# Schaltplan.net
KiCad netlist of a schematic drawn in EAGLE
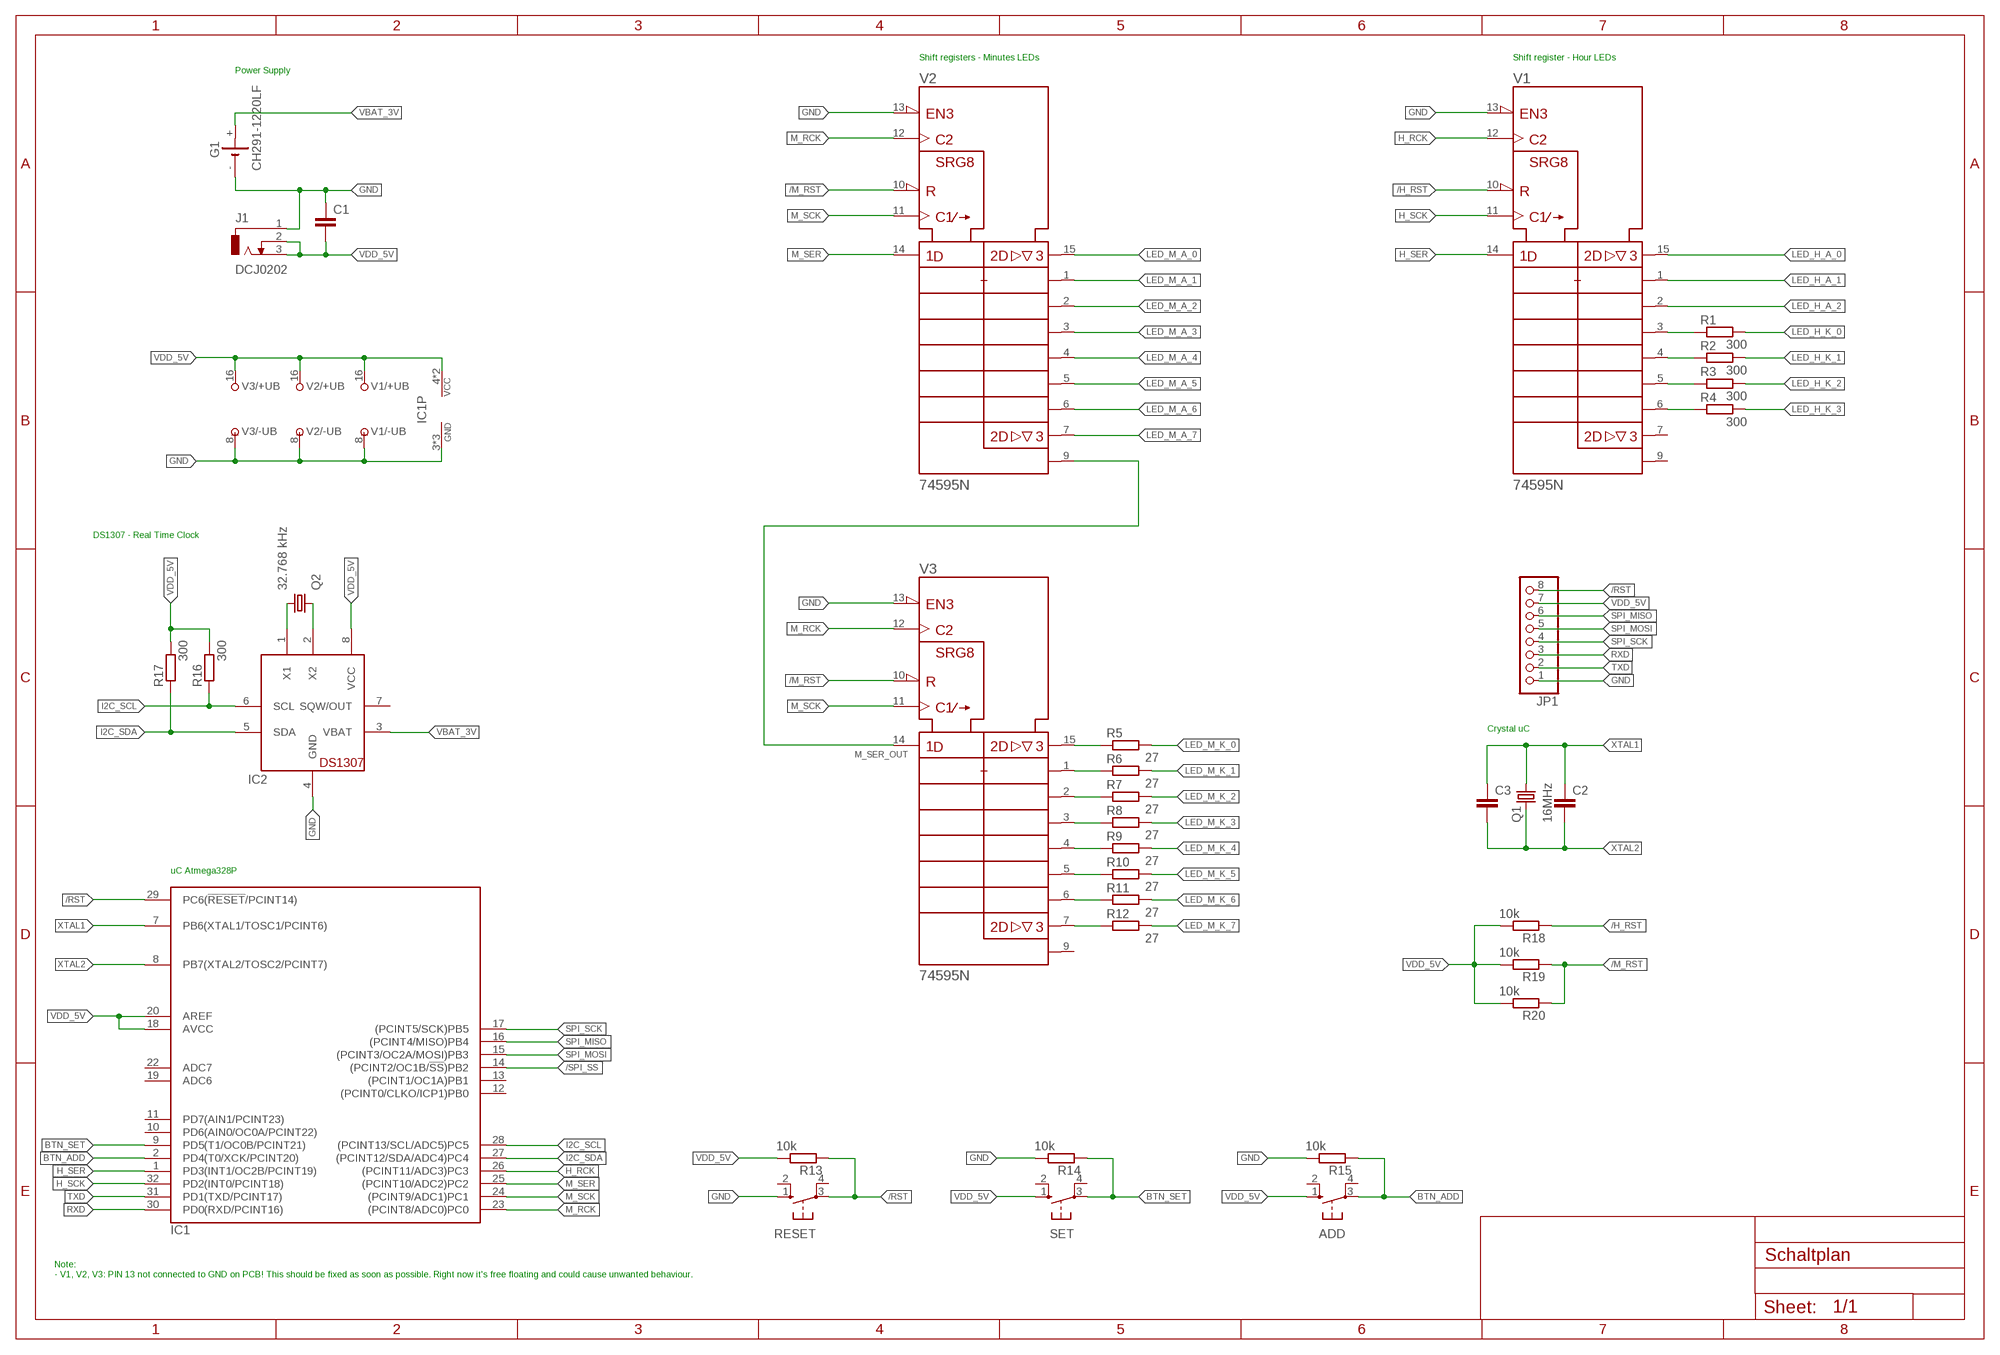
[diagram p0: schematic, sheet 1, part 1 of 2]
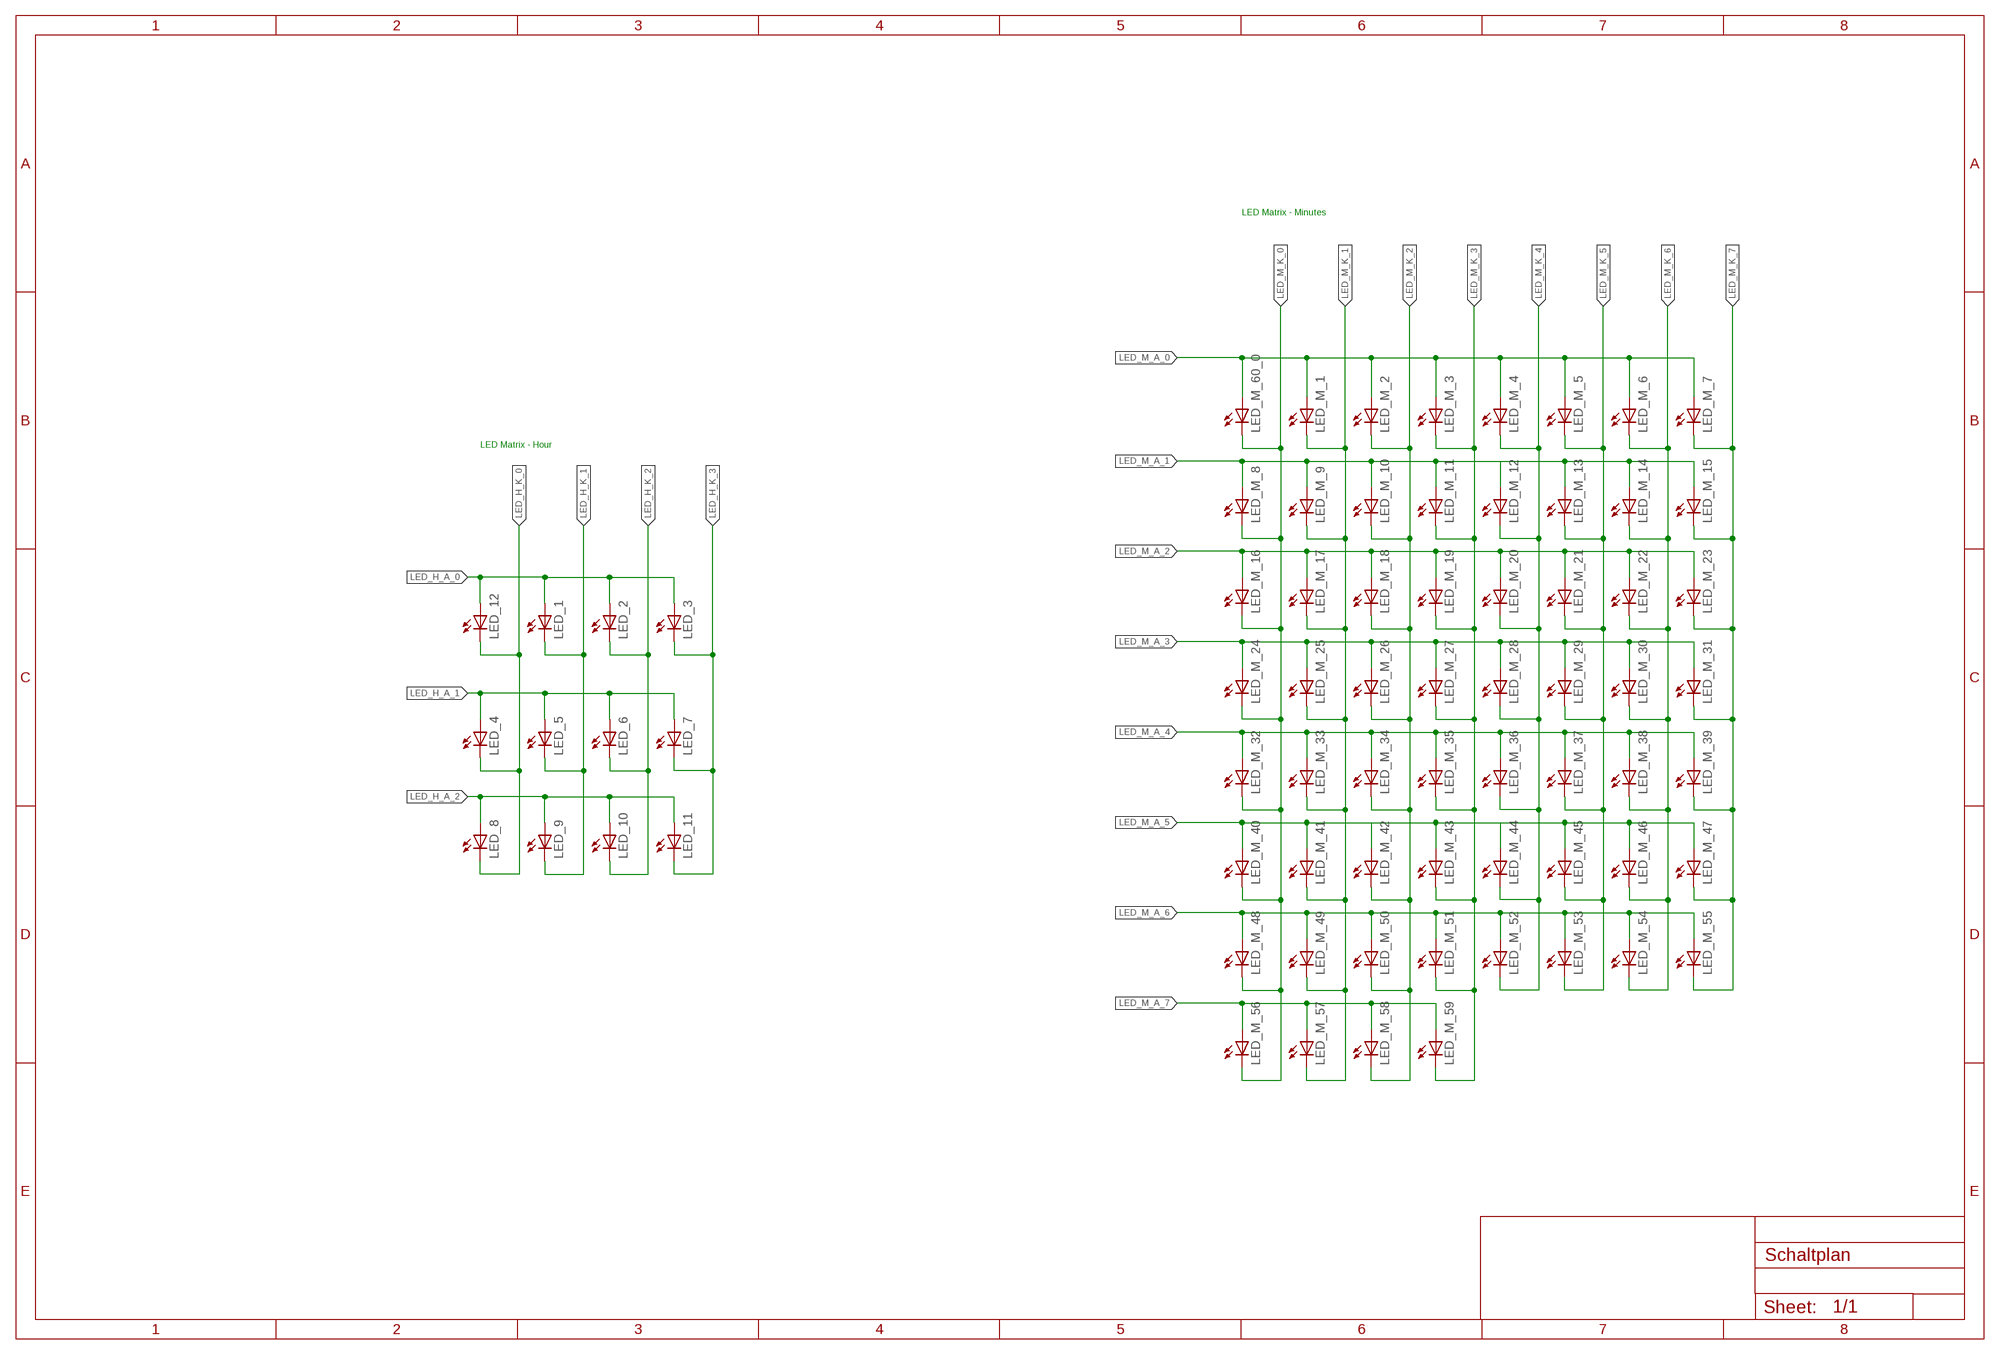
[diagram p1: schematic, sheet 1, part 2 of 2]

(export (version "E")
  (design (tool "Eeschema 10.0.6"))
  (components
    (comp (ref "ADD")
      (value "10-XX")
      (footprint "eagle-import:B3F-10XX")
      (fields (field (name "MPN") "B3F-1000"))
      (libsource (lib "eagle-import") (part "10-XX"))
    )
    (comp (ref "C1")
      (value "C-EUC1206")
      (footprint "eagle-import:C1206")
      (libsource (lib "eagle-import") (part "C-EUC1206"))
    )
    (comp (ref "C2")
      (value "C-EUC1206")
      (footprint "eagle-import:C1206")
      (libsource (lib "eagle-import") (part "C-EUC1206"))
    )
    (comp (ref "C3")
      (value "C-EUC1206")
      (footprint "eagle-import:C1206")
      (libsource (lib "eagle-import") (part "C-EUC1206"))
    )
    (comp (ref "G1")
      (value "CH291-1220LF")
      (footprint "eagle-import:CH291-1220LF")
      (libsource (lib "eagle-import") (part "CH291-1220LF"))
    )
    (comp (ref "IC1")
      (value "ATMEGA328P-AN")
      (footprint "eagle-import:QFP32_7X7_0.80")
      (libsource (lib "eagle-import") (part "ATMEGA8P-AN32"))
    )
    (comp (ref "IC2")
      (value "DS1307")
      (footprint "eagle-import:DIL08")
      (libsource (lib "eagle-import") (part "DS1307"))
    )
    (comp (ref "J1")
      (value "DCJ0202")
      (footprint "eagle-import:DCJ0202")
      (libsource (lib "eagle-import") (part "DCJ0202"))
    )
    (comp (ref "JP1")
      (value "PINHD-1X8")
      (footprint "eagle-import:1X08")
      (libsource (lib "eagle-import") (part "PINHD-1X8"))
    )
    (comp (ref "LED_1")
      (value "LED5MM")
      (footprint "eagle-import:LED5MM")
      (libsource (lib "eagle-import") (part "LED5MM"))
    )
    (comp (ref "LED_2")
      (value "LED5MM")
      (footprint "eagle-import:LED5MM")
      (libsource (lib "eagle-import") (part "LED5MM"))
    )
    (comp (ref "LED_3")
      (value "LED5MM")
      (footprint "eagle-import:LED5MM")
      (libsource (lib "eagle-import") (part "LED5MM"))
    )
    (comp (ref "LED_4")
      (value "LED5MM")
      (footprint "eagle-import:LED5MM")
      (libsource (lib "eagle-import") (part "LED5MM"))
    )
    (comp (ref "LED_5")
      (value "LED5MM")
      (footprint "eagle-import:LED5MM")
      (libsource (lib "eagle-import") (part "LED5MM"))
    )
    (comp (ref "LED_6")
      (value "LED5MM")
      (footprint "eagle-import:LED5MM")
      (libsource (lib "eagle-import") (part "LED5MM"))
    )
    (comp (ref "LED_7")
      (value "LED5MM")
      (footprint "eagle-import:LED5MM")
      (libsource (lib "eagle-import") (part "LED5MM"))
    )
    (comp (ref "LED_8")
      (value "LED5MM")
      (footprint "eagle-import:LED5MM")
      (libsource (lib "eagle-import") (part "LED5MM"))
    )
    (comp (ref "LED_9")
      (value "LED5MM")
      (footprint "eagle-import:LED5MM")
      (libsource (lib "eagle-import") (part "LED5MM"))
    )
    (comp (ref "LED_10")
      (value "LED5MM")
      (footprint "eagle-import:LED5MM")
      (libsource (lib "eagle-import") (part "LED5MM"))
    )
    (comp (ref "LED_11")
      (value "LED5MM")
      (footprint "eagle-import:LED5MM")
      (libsource (lib "eagle-import") (part "LED5MM"))
    )
    (comp (ref "LED_12")
      (value "LED5MM")
      (footprint "eagle-import:LED5MM")
      (libsource (lib "eagle-import") (part "LED5MM"))
    )
    (comp (ref "LED_M_1")
      (value "LED5MM")
      (footprint "eagle-import:LED5MM")
      (libsource (lib "eagle-import") (part "LED5MM"))
    )
    (comp (ref "LED_M_2")
      (value "LED5MM")
      (footprint "eagle-import:LED5MM")
      (libsource (lib "eagle-import") (part "LED5MM"))
    )
    (comp (ref "LED_M_3")
      (value "LED5MM")
      (footprint "eagle-import:LED5MM")
      (libsource (lib "eagle-import") (part "LED5MM"))
    )
    (comp (ref "LED_M_4")
      (value "LED5MM")
      (footprint "eagle-import:LED5MM")
      (libsource (lib "eagle-import") (part "LED5MM"))
    )
    (comp (ref "LED_M_5")
      (value "LED5MM")
      (footprint "eagle-import:LED5MM")
      (libsource (lib "eagle-import") (part "LED5MM"))
    )
    (comp (ref "LED_M_6")
      (value "LED5MM")
      (footprint "eagle-import:LED5MM")
      (libsource (lib "eagle-import") (part "LED5MM"))
    )
    (comp (ref "LED_M_7")
      (value "LED5MM")
      (footprint "eagle-import:LED5MM")
      (libsource (lib "eagle-import") (part "LED5MM"))
    )
    (comp (ref "LED_M_8")
      (value "LED5MM")
      (footprint "eagle-import:LED5MM")
      (libsource (lib "eagle-import") (part "LED5MM"))
    )
    (comp (ref "LED_M_9")
      (value "LED5MM")
      (footprint "eagle-import:LED5MM")
      (libsource (lib "eagle-import") (part "LED5MM"))
    )
    (comp (ref "LED_M_10")
      (value "LED5MM")
      (footprint "eagle-import:LED5MM")
      (libsource (lib "eagle-import") (part "LED5MM"))
    )
    (comp (ref "LED_M_11")
      (value "LED5MM")
      (footprint "eagle-import:LED5MM")
      (libsource (lib "eagle-import") (part "LED5MM"))
    )
    (comp (ref "LED_M_12")
      (value "LED5MM")
      (footprint "eagle-import:LED5MM")
      (libsource (lib "eagle-import") (part "LED5MM"))
    )
    (comp (ref "LED_M_13")
      (value "LED5MM")
      (footprint "eagle-import:LED5MM")
      (libsource (lib "eagle-import") (part "LED5MM"))
    )
    (comp (ref "LED_M_14")
      (value "LED5MM")
      (footprint "eagle-import:LED5MM")
      (libsource (lib "eagle-import") (part "LED5MM"))
    )
    (comp (ref "LED_M_15")
      (value "LED5MM")
      (footprint "eagle-import:LED5MM")
      (libsource (lib "eagle-import") (part "LED5MM"))
    )
    (comp (ref "LED_M_16")
      (value "LED5MM")
      (footprint "eagle-import:LED5MM")
      (libsource (lib "eagle-import") (part "LED5MM"))
    )
    (comp (ref "LED_M_17")
      (value "LED5MM")
      (footprint "eagle-import:LED5MM")
      (libsource (lib "eagle-import") (part "LED5MM"))
    )
    (comp (ref "LED_M_18")
      (value "LED5MM")
      (footprint "eagle-import:LED5MM")
      (libsource (lib "eagle-import") (part "LED5MM"))
    )
    (comp (ref "LED_M_19")
      (value "LED5MM")
      (footprint "eagle-import:LED5MM")
      (libsource (lib "eagle-import") (part "LED5MM"))
    )
    (comp (ref "LED_M_20")
      (value "LED5MM")
      (footprint "eagle-import:LED5MM")
      (libsource (lib "eagle-import") (part "LED5MM"))
    )
    (comp (ref "LED_M_21")
      (value "LED5MM")
      (footprint "eagle-import:LED5MM")
      (libsource (lib "eagle-import") (part "LED5MM"))
    )
    (comp (ref "LED_M_22")
      (value "LED5MM")
      (footprint "eagle-import:LED5MM")
      (libsource (lib "eagle-import") (part "LED5MM"))
    )
    (comp (ref "LED_M_23")
      (value "LED5MM")
      (footprint "eagle-import:LED5MM")
      (libsource (lib "eagle-import") (part "LED5MM"))
    )
    (comp (ref "LED_M_24")
      (value "LED5MM")
      (footprint "eagle-import:LED5MM")
      (libsource (lib "eagle-import") (part "LED5MM"))
    )
    (comp (ref "LED_M_25")
      (value "LED5MM")
      (footprint "eagle-import:LED5MM")
      (libsource (lib "eagle-import") (part "LED5MM"))
    )
    (comp (ref "LED_M_26")
      (value "LED5MM")
      (footprint "eagle-import:LED5MM")
      (libsource (lib "eagle-import") (part "LED5MM"))
    )
    (comp (ref "LED_M_27")
      (value "LED5MM")
      (footprint "eagle-import:LED5MM")
      (libsource (lib "eagle-import") (part "LED5MM"))
    )
    (comp (ref "LED_M_28")
      (value "LED5MM")
      (footprint "eagle-import:LED5MM")
      (libsource (lib "eagle-import") (part "LED5MM"))
    )
    (comp (ref "LED_M_29")
      (value "LED5MM")
      (footprint "eagle-import:LED5MM")
      (libsource (lib "eagle-import") (part "LED5MM"))
    )
    (comp (ref "LED_M_30")
      (value "LED5MM")
      (footprint "eagle-import:LED5MM")
      (libsource (lib "eagle-import") (part "LED5MM"))
    )
    (comp (ref "LED_M_31")
      (value "LED5MM")
      (footprint "eagle-import:LED5MM")
      (libsource (lib "eagle-import") (part "LED5MM"))
    )
    (comp (ref "LED_M_32")
      (value "LED5MM")
      (footprint "eagle-import:LED5MM")
      (libsource (lib "eagle-import") (part "LED5MM"))
    )
    (comp (ref "LED_M_33")
      (value "LED5MM")
      (footprint "eagle-import:LED5MM")
      (libsource (lib "eagle-import") (part "LED5MM"))
    )
    (comp (ref "LED_M_34")
      (value "LED5MM")
      (footprint "eagle-import:LED5MM")
      (libsource (lib "eagle-import") (part "LED5MM"))
    )
    (comp (ref "LED_M_35")
      (value "LED5MM")
      (footprint "eagle-import:LED5MM")
      (libsource (lib "eagle-import") (part "LED5MM"))
    )
    (comp (ref "LED_M_36")
      (value "LED5MM")
      (footprint "eagle-import:LED5MM")
      (libsource (lib "eagle-import") (part "LED5MM"))
    )
    (comp (ref "LED_M_37")
      (value "LED5MM")
      (footprint "eagle-import:LED5MM")
      (libsource (lib "eagle-import") (part "LED5MM"))
    )
    (comp (ref "LED_M_38")
      (value "LED5MM")
      (footprint "eagle-import:LED5MM")
      (libsource (lib "eagle-import") (part "LED5MM"))
    )
    (comp (ref "LED_M_39")
      (value "LED5MM")
      (footprint "eagle-import:LED5MM")
      (libsource (lib "eagle-import") (part "LED5MM"))
    )
    (comp (ref "LED_M_40")
      (value "LED5MM")
      (footprint "eagle-import:LED5MM")
      (libsource (lib "eagle-import") (part "LED5MM"))
    )
    (comp (ref "LED_M_41")
      (value "LED5MM")
      (footprint "eagle-import:LED5MM")
      (libsource (lib "eagle-import") (part "LED5MM"))
    )
    (comp (ref "LED_M_42")
      (value "LED5MM")
      (footprint "eagle-import:LED5MM")
      (libsource (lib "eagle-import") (part "LED5MM"))
    )
    (comp (ref "LED_M_43")
      (value "LED5MM")
      (footprint "eagle-import:LED5MM")
      (libsource (lib "eagle-import") (part "LED5MM"))
    )
    (comp (ref "LED_M_44")
      (value "LED5MM")
      (footprint "eagle-import:LED5MM")
      (libsource (lib "eagle-import") (part "LED5MM"))
    )
    (comp (ref "LED_M_45")
      (value "LED5MM")
      (footprint "eagle-import:LED5MM")
      (libsource (lib "eagle-import") (part "LED5MM"))
    )
    (comp (ref "LED_M_46")
      (value "LED5MM")
      (footprint "eagle-import:LED5MM")
      (libsource (lib "eagle-import") (part "LED5MM"))
    )
    (comp (ref "LED_M_47")
      (value "LED5MM")
      (footprint "eagle-import:LED5MM")
      (libsource (lib "eagle-import") (part "LED5MM"))
    )
    (comp (ref "LED_M_48")
      (value "LED5MM")
      (footprint "eagle-import:LED5MM")
      (libsource (lib "eagle-import") (part "LED5MM"))
    )
    (comp (ref "LED_M_49")
      (value "LED5MM")
      (footprint "eagle-import:LED5MM")
      (libsource (lib "eagle-import") (part "LED5MM"))
    )
    (comp (ref "LED_M_50")
      (value "LED5MM")
      (footprint "eagle-import:LED5MM")
      (libsource (lib "eagle-import") (part "LED5MM"))
    )
    (comp (ref "LED_M_51")
      (value "LED5MM")
      (footprint "eagle-import:LED5MM")
      (libsource (lib "eagle-import") (part "LED5MM"))
    )
    (comp (ref "LED_M_52")
      (value "LED5MM")
      (footprint "eagle-import:LED5MM")
      (libsource (lib "eagle-import") (part "LED5MM"))
    )
    (comp (ref "LED_M_53")
      (value "LED5MM")
      (footprint "eagle-import:LED5MM")
      (libsource (lib "eagle-import") (part "LED5MM"))
    )
    (comp (ref "LED_M_54")
      (value "LED5MM")
      (footprint "eagle-import:LED5MM")
      (libsource (lib "eagle-import") (part "LED5MM"))
    )
    (comp (ref "LED_M_55")
      (value "LED5MM")
      (footprint "eagle-import:LED5MM")
      (libsource (lib "eagle-import") (part "LED5MM"))
    )
    (comp (ref "LED_M_56")
      (value "LED5MM")
      (footprint "eagle-import:LED5MM")
      (libsource (lib "eagle-import") (part "LED5MM"))
    )
    (comp (ref "LED_M_57")
      (value "LED5MM")
      (footprint "eagle-import:LED5MM")
      (libsource (lib "eagle-import") (part "LED5MM"))
    )
    (comp (ref "LED_M_58")
      (value "LED5MM")
      (footprint "eagle-import:LED5MM")
      (libsource (lib "eagle-import") (part "LED5MM"))
    )
    (comp (ref "LED_M_59")
      (value "LED5MM")
      (footprint "eagle-import:LED5MM")
      (libsource (lib "eagle-import") (part "LED5MM"))
    )
    (comp (ref "LED_M_60_0")
      (value "LED5MM")
      (footprint "eagle-import:LED5MM")
      (libsource (lib "eagle-import") (part "LED5MM"))
    )
    (comp (ref "Q1")
      (value "16MHz")
      (footprint "eagle-import:HC49UP")
      (libsource (lib "eagle-import") (part "CRYSTALHC49UP"))
    )
    (comp (ref "Q2")
      (value "32.768 kHz")
      (footprint "eagle-import:TC26V")
      (libsource (lib "eagle-import") (part "crystal_204_CRYSTALTC26V"))
    )
    (comp (ref "R1")
      (value "300")
      (footprint "eagle-import:R5025")
      (libsource (lib "eagle-import") (part "R-EU_R5025"))
    )
    (comp (ref "R2")
      (value "300")
      (footprint "eagle-import:R5025")
      (libsource (lib "eagle-import") (part "R-EU_R5025"))
    )
    (comp (ref "R3")
      (value "300")
      (footprint "eagle-import:R5025")
      (libsource (lib "eagle-import") (part "R-EU_R5025"))
    )
    (comp (ref "R4")
      (value "300")
      (footprint "eagle-import:R5025")
      (libsource (lib "eagle-import") (part "R-EU_R5025"))
    )
    (comp (ref "R5")
      (value "27")
      (footprint "eagle-import:R5025")
      (libsource (lib "eagle-import") (part "R-EU_R5025"))
    )
    (comp (ref "R6")
      (value "27")
      (footprint "eagle-import:R5025")
      (libsource (lib "eagle-import") (part "R-EU_R5025"))
    )
    (comp (ref "R7")
      (value "27")
      (footprint "eagle-import:R5025")
      (libsource (lib "eagle-import") (part "R-EU_R5025"))
    )
    (comp (ref "R8")
      (value "27")
      (footprint "eagle-import:R5025")
      (libsource (lib "eagle-import") (part "R-EU_R5025"))
    )
    (comp (ref "R9")
      (value "27")
      (footprint "eagle-import:R5025")
      (libsource (lib "eagle-import") (part "R-EU_R5025"))
    )
    (comp (ref "R10")
      (value "27")
      (footprint "eagle-import:R5025")
      (libsource (lib "eagle-import") (part "R-EU_R5025"))
    )
    (comp (ref "R11")
      (value "27")
      (footprint "eagle-import:R5025")
      (libsource (lib "eagle-import") (part "R-EU_R5025"))
    )
    (comp (ref "R12")
      (value "27")
      (footprint "eagle-import:R5025")
      (libsource (lib "eagle-import") (part "R-EU_R5025"))
    )
    (comp (ref "R13")
      (value "10k")
      (footprint "eagle-import:R5025")
      (libsource (lib "eagle-import") (part "R-EU_R5025"))
    )
    (comp (ref "R14")
      (value "10k")
      (footprint "eagle-import:R5025")
      (libsource (lib "eagle-import") (part "R-EU_R5025"))
    )
    (comp (ref "R15")
      (value "10k")
      (footprint "eagle-import:R5025")
      (libsource (lib "eagle-import") (part "R-EU_R5025"))
    )
    (comp (ref "R16")
      (value "300")
      (footprint "eagle-import:R5025")
      (libsource (lib "eagle-import") (part "R-EU_R5025"))
    )
    (comp (ref "R17")
      (value "300")
      (footprint "eagle-import:R5025")
      (libsource (lib "eagle-import") (part "R-EU_R5025"))
    )
    (comp (ref "R18")
      (value "10k")
      (footprint "eagle-import:R5025")
      (libsource (lib "eagle-import") (part "R-EU_R5025"))
    )
    (comp (ref "R19")
      (value "10k")
      (footprint "eagle-import:R5025")
      (libsource (lib "eagle-import") (part "R-EU_R5025"))
    )
    (comp (ref "R20")
      (value "10k")
      (footprint "eagle-import:R5025")
      (libsource (lib "eagle-import") (part "R-EU_R5025"))
    )
    (comp (ref "RESET")
      (value "10-XX")
      (footprint "eagle-import:B3F-10XX")
      (fields (field (name "MPN") "B3F-1000"))
      (libsource (lib "eagle-import") (part "10-XX"))
    )
    (comp (ref "SET")
      (value "10-XX")
      (footprint "eagle-import:B3F-10XX")
      (fields (field (name "MPN") "B3F-1000"))
      (libsource (lib "eagle-import") (part "10-XX"))
    )
    (comp (ref "V1")
      (value "74595N")
      (footprint "eagle-import:DIL16")
      (libsource (lib "eagle-import") (part "74595N"))
    )
    (comp (ref "V2")
      (value "74595N")
      (footprint "eagle-import:DIL16")
      (libsource (lib "eagle-import") (part "74595N"))
    )
    (comp (ref "V3")
      (value "74595N")
      (footprint "eagle-import:DIL16")
      (libsource (lib "eagle-import") (part "74595N"))
    )
  )
  (nets
    (net (code "1") (name "/M_SER_OUT") (class "Default")
      (node (ref "V2") (pin "9") (pinfunction "QH*_9") (pintype "output"))
      (node (ref "V3") (pin "14") (pinfunction "SER_14") (pintype "input"))
    )
    (net (code "2") (name "BTN_ADD") (class "Default")
      (node (ref "ADD") (pin "3") (pinfunction "P_3") (pintype "passive"))
      (node (ref "IC1") (pin "2") (pinfunction "PD4(T0/XCK/PCINT20)_2") (pintype "bidirectional"))
      (node (ref "R15") (pin "1") (pinfunction "1_1") (pintype "passive"))
    )
    (net (code "3") (name "BTN_SET") (class "Default")
      (node (ref "IC1") (pin "9") (pinfunction "PD5(T1/OC0B/PCINT21)_9") (pintype "bidirectional"))
      (node (ref "R14") (pin "1") (pinfunction "1_1") (pintype "passive"))
      (node (ref "SET") (pin "3") (pinfunction "P_3") (pintype "passive"))
    )
    (net (code "4") (name "GND") (class "Default")
      (node (ref "C1") (pin "1") (pinfunction "1_1") (pintype "passive"))
      (node (ref "G1") (pin "-") (pinfunction "-_-") (pintype "passive"))
      (node (ref "IC1") (pin "21") (pinfunction "GND_21") (pintype "power_in"))
      (node (ref "IC1") (pin "3") (pinfunction "GND_3") (pintype "power_in"))
      (node (ref "IC1") (pin "5") (pinfunction "GND_5") (pintype "power_in"))
      (node (ref "IC2") (pin "4") (pinfunction "GND_4") (pintype "power_in"))
      (node (ref "J1") (pin "1") (pinfunction "1_1") (pintype "passive"))
      (node (ref "JP1") (pin "1") (pinfunction "1_1") (pintype "passive"))
      (node (ref "R14") (pin "2") (pinfunction "2_2") (pintype "passive"))
      (node (ref "R15") (pin "2") (pinfunction "2_2") (pintype "passive"))
      (node (ref "RESET") (pin "1") (pinfunction "S_1") (pintype "passive"))
      (node (ref "V1") (pin "13") (pinfunction "~{G}_13") (pintype "input"))
      (node (ref "V1") (pin "8") (pinfunction "-UB_8") (pintype "power_in"))
      (node (ref "V2") (pin "13") (pinfunction "~{G}_13") (pintype "input"))
      (node (ref "V2") (pin "8") (pinfunction "-UB_8") (pintype "power_in"))
      (node (ref "V3") (pin "13") (pinfunction "~{G}_13") (pintype "input"))
      (node (ref "V3") (pin "8") (pinfunction "-UB_8") (pintype "power_in"))
    )
    (net (code "5") (name "H_RCK") (class "Default")
      (node (ref "IC1") (pin "26") (pinfunction "(PCINT11/ADC3)PC3_26") (pintype "bidirectional"))
      (node (ref "V1") (pin "12") (pinfunction "RCK_12") (pintype "input"))
    )
    (net (code "6") (name "H_SCK") (class "Default")
      (node (ref "IC1") (pin "32") (pinfunction "PD2(INT0/PCINT18)_32") (pintype "bidirectional"))
      (node (ref "V1") (pin "11") (pinfunction "SRCK_11") (pintype "input"))
    )
    (net (code "7") (name "H_SER") (class "Default")
      (node (ref "IC1") (pin "1") (pinfunction "PD3(INT1/OC2B/PCINT19)_1") (pintype "bidirectional"))
      (node (ref "V1") (pin "14") (pinfunction "SER_14") (pintype "input"))
    )
    (net (code "8") (name "I2C_SCL") (class "Default")
      (node (ref "IC1") (pin "28") (pinfunction "(PCINT13/SCL/ADC5)PC5_28") (pintype "bidirectional"))
      (node (ref "IC2") (pin "6") (pinfunction "SCL_6") (pintype "bidirectional"))
      (node (ref "R16") (pin "1") (pinfunction "1_1") (pintype "passive"))
    )
    (net (code "9") (name "I2C_SDA") (class "Default")
      (node (ref "IC1") (pin "27") (pinfunction "(PCINT12/SDA/ADC4)PC4_27") (pintype "bidirectional"))
      (node (ref "IC2") (pin "5") (pinfunction "SDA_5") (pintype "bidirectional"))
      (node (ref "R17") (pin "1") (pinfunction "1_1") (pintype "passive"))
    )
    (net (code "10") (name "LED_H_A_0") (class "Default")
      (node (ref "LED_1") (pin "A") (pinfunction "A_A") (pintype "passive"))
      (node (ref "LED_12") (pin "A") (pinfunction "A_A") (pintype "passive"))
      (node (ref "LED_2") (pin "A") (pinfunction "A_A") (pintype "passive"))
      (node (ref "LED_3") (pin "A") (pinfunction "A_A") (pintype "passive"))
      (node (ref "V1") (pin "15") (pinfunction "QA_15") (pintype "tri_state"))
    )
    (net (code "11") (name "LED_H_A_1") (class "Default")
      (node (ref "LED_4") (pin "A") (pinfunction "A_A") (pintype "passive"))
      (node (ref "LED_5") (pin "A") (pinfunction "A_A") (pintype "passive"))
      (node (ref "LED_6") (pin "A") (pinfunction "A_A") (pintype "passive"))
      (node (ref "LED_7") (pin "A") (pinfunction "A_A") (pintype "passive"))
      (node (ref "V1") (pin "1") (pinfunction "QB_1") (pintype "tri_state"))
    )
    (net (code "12") (name "LED_H_A_2") (class "Default")
      (node (ref "LED_10") (pin "A") (pinfunction "A_A") (pintype "passive"))
      (node (ref "LED_11") (pin "A") (pinfunction "A_A") (pintype "passive"))
      (node (ref "LED_8") (pin "A") (pinfunction "A_A") (pintype "passive"))
      (node (ref "LED_9") (pin "A") (pinfunction "A_A") (pintype "passive"))
      (node (ref "V1") (pin "2") (pinfunction "QC_2") (pintype "tri_state"))
    )
    (net (code "13") (name "LED_H_K_0") (class "Default")
      (node (ref "LED_12") (pin "K") (pinfunction "C_K") (pintype "passive"))
      (node (ref "LED_4") (pin "K") (pinfunction "C_K") (pintype "passive"))
      (node (ref "LED_8") (pin "K") (pinfunction "C_K") (pintype "passive"))
      (node (ref "R1") (pin "2") (pinfunction "2_2") (pintype "passive"))
    )
    (net (code "14") (name "LED_H_K_1") (class "Default")
      (node (ref "LED_1") (pin "K") (pinfunction "C_K") (pintype "passive"))
      (node (ref "LED_5") (pin "K") (pinfunction "C_K") (pintype "passive"))
      (node (ref "LED_9") (pin "K") (pinfunction "C_K") (pintype "passive"))
      (node (ref "R2") (pin "2") (pinfunction "2_2") (pintype "passive"))
    )
    (net (code "15") (name "LED_H_K_2") (class "Default")
      (node (ref "LED_10") (pin "K") (pinfunction "C_K") (pintype "passive"))
      (node (ref "LED_2") (pin "K") (pinfunction "C_K") (pintype "passive"))
      (node (ref "LED_6") (pin "K") (pinfunction "C_K") (pintype "passive"))
      (node (ref "R3") (pin "2") (pinfunction "2_2") (pintype "passive"))
    )
    (net (code "16") (name "LED_H_K_3") (class "Default")
      (node (ref "LED_11") (pin "K") (pinfunction "C_K") (pintype "passive"))
      (node (ref "LED_3") (pin "K") (pinfunction "C_K") (pintype "passive"))
      (node (ref "LED_7") (pin "K") (pinfunction "C_K") (pintype "passive"))
      (node (ref "R4") (pin "2") (pinfunction "2_2") (pintype "passive"))
    )
    (net (code "17") (name "LED_M_A_0") (class "Default")
      (node (ref "LED_M_1") (pin "A") (pinfunction "A_A") (pintype "passive"))
      (node (ref "LED_M_2") (pin "A") (pinfunction "A_A") (pintype "passive"))
      (node (ref "LED_M_3") (pin "A") (pinfunction "A_A") (pintype "passive"))
      (node (ref "LED_M_4") (pin "A") (pinfunction "A_A") (pintype "passive"))
      (node (ref "LED_M_5") (pin "A") (pinfunction "A_A") (pintype "passive"))
      (node (ref "LED_M_6") (pin "A") (pinfunction "A_A") (pintype "passive"))
      (node (ref "LED_M_60_0") (pin "A") (pinfunction "A_A") (pintype "passive"))
      (node (ref "LED_M_7") (pin "A") (pinfunction "A_A") (pintype "passive"))
      (node (ref "V2") (pin "15") (pinfunction "QA_15") (pintype "tri_state"))
    )
    (net (code "18") (name "LED_M_A_1") (class "Default")
      (node (ref "LED_M_10") (pin "A") (pinfunction "A_A") (pintype "passive"))
      (node (ref "LED_M_11") (pin "A") (pinfunction "A_A") (pintype "passive"))
      (node (ref "LED_M_12") (pin "A") (pinfunction "A_A") (pintype "passive"))
      (node (ref "LED_M_13") (pin "A") (pinfunction "A_A") (pintype "passive"))
      (node (ref "LED_M_14") (pin "A") (pinfunction "A_A") (pintype "passive"))
      (node (ref "LED_M_15") (pin "A") (pinfunction "A_A") (pintype "passive"))
      (node (ref "LED_M_8") (pin "A") (pinfunction "A_A") (pintype "passive"))
      (node (ref "LED_M_9") (pin "A") (pinfunction "A_A") (pintype "passive"))
      (node (ref "V2") (pin "1") (pinfunction "QB_1") (pintype "tri_state"))
    )
    (net (code "19") (name "LED_M_A_2") (class "Default")
      (node (ref "LED_M_16") (pin "A") (pinfunction "A_A") (pintype "passive"))
      (node (ref "LED_M_17") (pin "A") (pinfunction "A_A") (pintype "passive"))
      (node (ref "LED_M_18") (pin "A") (pinfunction "A_A") (pintype "passive"))
      (node (ref "LED_M_19") (pin "A") (pinfunction "A_A") (pintype "passive"))
      (node (ref "LED_M_20") (pin "A") (pinfunction "A_A") (pintype "passive"))
      (node (ref "LED_M_21") (pin "A") (pinfunction "A_A") (pintype "passive"))
      (node (ref "LED_M_22") (pin "A") (pinfunction "A_A") (pintype "passive"))
      (node (ref "LED_M_23") (pin "A") (pinfunction "A_A") (pintype "passive"))
      (node (ref "V2") (pin "2") (pinfunction "QC_2") (pintype "tri_state"))
    )
    (net (code "20") (name "LED_M_A_3") (class "Default")
      (node (ref "LED_M_24") (pin "A") (pinfunction "A_A") (pintype "passive"))
      (node (ref "LED_M_25") (pin "A") (pinfunction "A_A") (pintype "passive"))
      (node (ref "LED_M_26") (pin "A") (pinfunction "A_A") (pintype "passive"))
      (node (ref "LED_M_27") (pin "A") (pinfunction "A_A") (pintype "passive"))
      (node (ref "LED_M_28") (pin "A") (pinfunction "A_A") (pintype "passive"))
      (node (ref "LED_M_29") (pin "A") (pinfunction "A_A") (pintype "passive"))
      (node (ref "LED_M_30") (pin "A") (pinfunction "A_A") (pintype "passive"))
      (node (ref "LED_M_31") (pin "A") (pinfunction "A_A") (pintype "passive"))
      (node (ref "V2") (pin "3") (pinfunction "QD_3") (pintype "tri_state"))
    )
    (net (code "21") (name "LED_M_A_4") (class "Default")
      (node (ref "LED_M_32") (pin "A") (pinfunction "A_A") (pintype "passive"))
      (node (ref "LED_M_33") (pin "A") (pinfunction "A_A") (pintype "passive"))
      (node (ref "LED_M_34") (pin "A") (pinfunction "A_A") (pintype "passive"))
      (node (ref "LED_M_35") (pin "A") (pinfunction "A_A") (pintype "passive"))
      (node (ref "LED_M_36") (pin "A") (pinfunction "A_A") (pintype "passive"))
      (node (ref "LED_M_37") (pin "A") (pinfunction "A_A") (pintype "passive"))
      (node (ref "LED_M_38") (pin "A") (pinfunction "A_A") (pintype "passive"))
      (node (ref "LED_M_39") (pin "A") (pinfunction "A_A") (pintype "passive"))
      (node (ref "V2") (pin "4") (pinfunction "QE_4") (pintype "tri_state"))
    )
    (net (code "22") (name "LED_M_A_5") (class "Default")
      (node (ref "LED_M_40") (pin "A") (pinfunction "A_A") (pintype "passive"))
      (node (ref "LED_M_41") (pin "A") (pinfunction "A_A") (pintype "passive"))
      (node (ref "LED_M_42") (pin "A") (pinfunction "A_A") (pintype "passive"))
      (node (ref "LED_M_43") (pin "A") (pinfunction "A_A") (pintype "passive"))
      (node (ref "LED_M_44") (pin "A") (pinfunction "A_A") (pintype "passive"))
      (node (ref "LED_M_45") (pin "A") (pinfunction "A_A") (pintype "passive"))
      (node (ref "LED_M_46") (pin "A") (pinfunction "A_A") (pintype "passive"))
      (node (ref "LED_M_47") (pin "A") (pinfunction "A_A") (pintype "passive"))
      (node (ref "V2") (pin "5") (pinfunction "QF_5") (pintype "tri_state"))
    )
    (net (code "23") (name "LED_M_A_6") (class "Default")
      (node (ref "LED_M_48") (pin "A") (pinfunction "A_A") (pintype "passive"))
      (node (ref "LED_M_49") (pin "A") (pinfunction "A_A") (pintype "passive"))
      (node (ref "LED_M_50") (pin "A") (pinfunction "A_A") (pintype "passive"))
      (node (ref "LED_M_51") (pin "A") (pinfunction "A_A") (pintype "passive"))
      (node (ref "LED_M_52") (pin "A") (pinfunction "A_A") (pintype "passive"))
      (node (ref "LED_M_53") (pin "A") (pinfunction "A_A") (pintype "passive"))
      (node (ref "LED_M_54") (pin "A") (pinfunction "A_A") (pintype "passive"))
      (node (ref "LED_M_55") (pin "A") (pinfunction "A_A") (pintype "passive"))
      (node (ref "V2") (pin "6") (pinfunction "QG_6") (pintype "tri_state"))
    )
    (net (code "24") (name "LED_M_A_7") (class "Default")
      (node (ref "LED_M_56") (pin "A") (pinfunction "A_A") (pintype "passive"))
      (node (ref "LED_M_57") (pin "A") (pinfunction "A_A") (pintype "passive"))
      (node (ref "LED_M_58") (pin "A") (pinfunction "A_A") (pintype "passive"))
      (node (ref "LED_M_59") (pin "A") (pinfunction "A_A") (pintype "passive"))
      (node (ref "V2") (pin "7") (pinfunction "QH_7") (pintype "tri_state"))
    )
    (net (code "25") (name "LED_M_K_0") (class "Default")
      (node (ref "LED_M_16") (pin "K") (pinfunction "C_K") (pintype "passive"))
      (node (ref "LED_M_24") (pin "K") (pinfunction "C_K") (pintype "passive"))
      (node (ref "LED_M_32") (pin "K") (pinfunction "C_K") (pintype "passive"))
      (node (ref "LED_M_40") (pin "K") (pinfunction "C_K") (pintype "passive"))
      (node (ref "LED_M_48") (pin "K") (pinfunction "C_K") (pintype "passive"))
      (node (ref "LED_M_56") (pin "K") (pinfunction "C_K") (pintype "passive"))
      (node (ref "LED_M_60_0") (pin "K") (pinfunction "C_K") (pintype "passive"))
      (node (ref "LED_M_8") (pin "K") (pinfunction "C_K") (pintype "passive"))
      (node (ref "R5") (pin "2") (pinfunction "2_2") (pintype "passive"))
    )
    (net (code "26") (name "LED_M_K_1") (class "Default")
      (node (ref "LED_M_1") (pin "K") (pinfunction "C_K") (pintype "passive"))
      (node (ref "LED_M_17") (pin "K") (pinfunction "C_K") (pintype "passive"))
      (node (ref "LED_M_25") (pin "K") (pinfunction "C_K") (pintype "passive"))
      (node (ref "LED_M_33") (pin "K") (pinfunction "C_K") (pintype "passive"))
      (node (ref "LED_M_41") (pin "K") (pinfunction "C_K") (pintype "passive"))
      (node (ref "LED_M_49") (pin "K") (pinfunction "C_K") (pintype "passive"))
      (node (ref "LED_M_57") (pin "K") (pinfunction "C_K") (pintype "passive"))
      (node (ref "LED_M_9") (pin "K") (pinfunction "C_K") (pintype "passive"))
      (node (ref "R6") (pin "2") (pinfunction "2_2") (pintype "passive"))
    )
    (net (code "27") (name "LED_M_K_2") (class "Default")
      (node (ref "LED_M_10") (pin "K") (pinfunction "C_K") (pintype "passive"))
      (node (ref "LED_M_18") (pin "K") (pinfunction "C_K") (pintype "passive"))
      (node (ref "LED_M_2") (pin "K") (pinfunction "C_K") (pintype "passive"))
      (node (ref "LED_M_26") (pin "K") (pinfunction "C_K") (pintype "passive"))
      (node (ref "LED_M_34") (pin "K") (pinfunction "C_K") (pintype "passive"))
      (node (ref "LED_M_42") (pin "K") (pinfunction "C_K") (pintype "passive"))
      (node (ref "LED_M_50") (pin "K") (pinfunction "C_K") (pintype "passive"))
      (node (ref "LED_M_58") (pin "K") (pinfunction "C_K") (pintype "passive"))
      (node (ref "R7") (pin "2") (pinfunction "2_2") (pintype "passive"))
    )
    (net (code "28") (name "LED_M_K_3") (class "Default")
      (node (ref "LED_M_11") (pin "K") (pinfunction "C_K") (pintype "passive"))
      (node (ref "LED_M_19") (pin "K") (pinfunction "C_K") (pintype "passive"))
      (node (ref "LED_M_27") (pin "K") (pinfunction "C_K") (pintype "passive"))
      (node (ref "LED_M_3") (pin "K") (pinfunction "C_K") (pintype "passive"))
      (node (ref "LED_M_35") (pin "K") (pinfunction "C_K") (pintype "passive"))
      (node (ref "LED_M_43") (pin "K") (pinfunction "C_K") (pintype "passive"))
      (node (ref "LED_M_51") (pin "K") (pinfunction "C_K") (pintype "passive"))
      (node (ref "LED_M_59") (pin "K") (pinfunction "C_K") (pintype "passive"))
      (node (ref "R8") (pin "2") (pinfunction "2_2") (pintype "passive"))
    )
    (net (code "29") (name "LED_M_K_4") (class "Default")
      (node (ref "LED_M_12") (pin "K") (pinfunction "C_K") (pintype "passive"))
      (node (ref "LED_M_20") (pin "K") (pinfunction "C_K") (pintype "passive"))
      (node (ref "LED_M_28") (pin "K") (pinfunction "C_K") (pintype "passive"))
      (node (ref "LED_M_36") (pin "K") (pinfunction "C_K") (pintype "passive"))
      (node (ref "LED_M_4") (pin "K") (pinfunction "C_K") (pintype "passive"))
      (node (ref "LED_M_44") (pin "K") (pinfunction "C_K") (pintype "passive"))
      (node (ref "LED_M_52") (pin "K") (pinfunction "C_K") (pintype "passive"))
      (node (ref "R9") (pin "2") (pinfunction "2_2") (pintype "passive"))
    )
    (net (code "30") (name "LED_M_K_5") (class "Default")
      (node (ref "LED_M_13") (pin "K") (pinfunction "C_K") (pintype "passive"))
      (node (ref "LED_M_21") (pin "K") (pinfunction "C_K") (pintype "passive"))
      (node (ref "LED_M_29") (pin "K") (pinfunction "C_K") (pintype "passive"))
      (node (ref "LED_M_37") (pin "K") (pinfunction "C_K") (pintype "passive"))
      (node (ref "LED_M_45") (pin "K") (pinfunction "C_K") (pintype "passive"))
      (node (ref "LED_M_5") (pin "K") (pinfunction "C_K") (pintype "passive"))
      (node (ref "LED_M_53") (pin "K") (pinfunction "C_K") (pintype "passive"))
      (node (ref "R10") (pin "2") (pinfunction "2_2") (pintype "passive"))
    )
    (net (code "31") (name "LED_M_K_6") (class "Default")
      (node (ref "LED_M_14") (pin "K") (pinfunction "C_K") (pintype "passive"))
      (node (ref "LED_M_22") (pin "K") (pinfunction "C_K") (pintype "passive"))
      (node (ref "LED_M_30") (pin "K") (pinfunction "C_K") (pintype "passive"))
      (node (ref "LED_M_38") (pin "K") (pinfunction "C_K") (pintype "passive"))
      (node (ref "LED_M_46") (pin "K") (pinfunction "C_K") (pintype "passive"))
      (node (ref "LED_M_54") (pin "K") (pinfunction "C_K") (pintype "passive"))
      (node (ref "LED_M_6") (pin "K") (pinfunction "C_K") (pintype "passive"))
      (node (ref "R11") (pin "2") (pinfunction "2_2") (pintype "passive"))
    )
    (net (code "32") (name "LED_M_K_7") (class "Default")
      (node (ref "LED_M_15") (pin "K") (pinfunction "C_K") (pintype "passive"))
      (node (ref "LED_M_23") (pin "K") (pinfunction "C_K") (pintype "passive"))
      (node (ref "LED_M_31") (pin "K") (pinfunction "C_K") (pintype "passive"))
      (node (ref "LED_M_39") (pin "K") (pinfunction "C_K") (pintype "passive"))
      (node (ref "LED_M_47") (pin "K") (pinfunction "C_K") (pintype "passive"))
      (node (ref "LED_M_55") (pin "K") (pinfunction "C_K") (pintype "passive"))
      (node (ref "LED_M_7") (pin "K") (pinfunction "C_K") (pintype "passive"))
      (node (ref "R12") (pin "2") (pinfunction "2_2") (pintype "passive"))
    )
    (net (code "33") (name "M_RCK") (class "Default")
      (node (ref "IC1") (pin "23") (pinfunction "(PCINT8/ADC0)PC0_23") (pintype "bidirectional"))
      (node (ref "V2") (pin "12") (pinfunction "RCK_12") (pintype "input"))
      (node (ref "V3") (pin "12") (pinfunction "RCK_12") (pintype "input"))
    )
    (net (code "34") (name "M_SCK") (class "Default")
      (node (ref "IC1") (pin "24") (pinfunction "(PCINT9/ADC1)PC1_24") (pintype "bidirectional"))
      (node (ref "V2") (pin "11") (pinfunction "SRCK_11") (pintype "input"))
      (node (ref "V3") (pin "11") (pinfunction "SRCK_11") (pintype "input"))
    )
    (net (code "35") (name "M_SER") (class "Default")
      (node (ref "IC1") (pin "25") (pinfunction "(PCINT10/ADC2)PC2_25") (pintype "bidirectional"))
      (node (ref "V2") (pin "14") (pinfunction "SER_14") (pintype "input"))
    )
    (net (code "36") (name "Net-(IC2-X1)") (class "Default")
      (node (ref "IC2") (pin "1") (pinfunction "X1_1") (pintype "passive"))
      (node (ref "Q2") (pin "1") (pinfunction "1_1") (pintype "passive"))
    )
    (net (code "37") (name "Net-(IC2-X2)") (class "Default")
      (node (ref "IC2") (pin "2") (pinfunction "X2_2") (pintype "passive"))
      (node (ref "Q2") (pin "2") (pinfunction "2_2") (pintype "passive"))
    )
    (net (code "38") (name "Net-(V1C-QD)") (class "Default")
      (node (ref "R1") (pin "1") (pinfunction "1_1") (pintype "passive"))
      (node (ref "V1") (pin "3") (pinfunction "QD_3") (pintype "tri_state"))
    )
    (net (code "39") (name "Net-(V1C-QE)") (class "Default")
      (node (ref "R2") (pin "1") (pinfunction "1_1") (pintype "passive"))
      (node (ref "V1") (pin "4") (pinfunction "QE_4") (pintype "tri_state"))
    )
    (net (code "40") (name "Net-(V1C-QF)") (class "Default")
      (node (ref "R3") (pin "1") (pinfunction "1_1") (pintype "passive"))
      (node (ref "V1") (pin "5") (pinfunction "QF_5") (pintype "tri_state"))
    )
    (net (code "41") (name "Net-(V1C-QG)") (class "Default")
      (node (ref "R4") (pin "1") (pinfunction "1_1") (pintype "passive"))
      (node (ref "V1") (pin "6") (pinfunction "QG_6") (pintype "tri_state"))
    )
    (net (code "42") (name "Net-(V3C-QA)") (class "Default")
      (node (ref "R5") (pin "1") (pinfunction "1_1") (pintype "passive"))
      (node (ref "V3") (pin "15") (pinfunction "QA_15") (pintype "tri_state"))
    )
    (net (code "43") (name "Net-(V3C-QB)") (class "Default")
      (node (ref "R6") (pin "1") (pinfunction "1_1") (pintype "passive"))
      (node (ref "V3") (pin "1") (pinfunction "QB_1") (pintype "tri_state"))
    )
    (net (code "44") (name "Net-(V3C-QC)") (class "Default")
      (node (ref "R7") (pin "1") (pinfunction "1_1") (pintype "passive"))
      (node (ref "V3") (pin "2") (pinfunction "QC_2") (pintype "tri_state"))
    )
    (net (code "45") (name "Net-(V3C-QD)") (class "Default")
      (node (ref "R8") (pin "1") (pinfunction "1_1") (pintype "passive"))
      (node (ref "V3") (pin "3") (pinfunction "QD_3") (pintype "tri_state"))
    )
    (net (code "46") (name "Net-(V3C-QE)") (class "Default")
      (node (ref "R9") (pin "1") (pinfunction "1_1") (pintype "passive"))
      (node (ref "V3") (pin "4") (pinfunction "QE_4") (pintype "tri_state"))
    )
    (net (code "47") (name "Net-(V3C-QF)") (class "Default")
      (node (ref "R10") (pin "1") (pinfunction "1_1") (pintype "passive"))
      (node (ref "V3") (pin "5") (pinfunction "QF_5") (pintype "tri_state"))
    )
    (net (code "48") (name "Net-(V3C-QG)") (class "Default")
      (node (ref "R11") (pin "1") (pinfunction "1_1") (pintype "passive"))
      (node (ref "V3") (pin "6") (pinfunction "QG_6") (pintype "tri_state"))
    )
    (net (code "49") (name "Net-(V3C-QH)") (class "Default")
      (node (ref "R12") (pin "1") (pinfunction "1_1") (pintype "passive"))
      (node (ref "V3") (pin "7") (pinfunction "QH_7") (pintype "tri_state"))
    )
    (net (code "50") (name "RXD") (class "Default")
      (node (ref "IC1") (pin "30") (pinfunction "PD0(RXD/PCINT16)_30") (pintype "bidirectional"))
      (node (ref "JP1") (pin "3") (pinfunction "3_3") (pintype "passive"))
    )
    (net (code "51") (name "SPI_MISO") (class "Default")
      (node (ref "IC1") (pin "16") (pinfunction "(PCINT4/MISO)PB4_16") (pintype "bidirectional"))
      (node (ref "JP1") (pin "6") (pinfunction "6_6") (pintype "passive"))
    )
    (net (code "52") (name "SPI_MOSI") (class "Default")
      (node (ref "IC1") (pin "15") (pinfunction "(PCINT3/OC2A/MOSI)PB3_15") (pintype "bidirectional"))
      (node (ref "JP1") (pin "5") (pinfunction "5_5") (pintype "passive"))
    )
    (net (code "53") (name "SPI_SCK") (class "Default")
      (node (ref "IC1") (pin "17") (pinfunction "(PCINT5/SCK)PB5_17") (pintype "bidirectional"))
      (node (ref "JP1") (pin "4") (pinfunction "4_4") (pintype "passive"))
    )
    (net (code "54") (name "TXD") (class "Default")
      (node (ref "IC1") (pin "31") (pinfunction "PD1(TXD/PCINT17)_31") (pintype "bidirectional"))
      (node (ref "JP1") (pin "2") (pinfunction "2_2") (pintype "passive"))
    )
    (net (code "55") (name "VBAT_3V") (class "Default")
      (node (ref "G1") (pin "+") (pinfunction "+_+") (pintype "passive"))
      (node (ref "IC2") (pin "3") (pinfunction "VBAT_3") (pintype "power_in"))
    )
    (net (code "56") (name "VDD_5V") (class "Default")
      (node (ref "ADD") (pin "1") (pinfunction "S_1") (pintype "passive"))
      (node (ref "C1") (pin "2") (pinfunction "2_2") (pintype "passive"))
      (node (ref "IC1") (pin "18") (pinfunction "AVCC_18") (pintype "power_in"))
      (node (ref "IC1") (pin "20") (pinfunction "AREF_20") (pintype "passive"))
      (node (ref "IC1") (pin "4") (pinfunction "VCC_4") (pintype "power_in"))
      (node (ref "IC1") (pin "6") (pinfunction "VCC_6") (pintype "power_in"))
      (node (ref "IC2") (pin "8") (pinfunction "VCC_8") (pintype "power_in"))
      (node (ref "J1") (pin "2") (pinfunction "2_2") (pintype "passive"))
      (node (ref "J1") (pin "3") (pinfunction "3_3") (pintype "passive"))
      (node (ref "JP1") (pin "7") (pinfunction "7_7") (pintype "passive"))
      (node (ref "R13") (pin "2") (pinfunction "2_2") (pintype "passive"))
      (node (ref "R16") (pin "2") (pinfunction "2_2") (pintype "passive"))
      (node (ref "R17") (pin "2") (pinfunction "2_2") (pintype "passive"))
      (node (ref "R18") (pin "2") (pinfunction "2_2") (pintype "passive"))
      (node (ref "R19") (pin "2") (pinfunction "2_2") (pintype "passive"))
      (node (ref "R20") (pin "2") (pinfunction "2_2") (pintype "passive"))
      (node (ref "SET") (pin "1") (pinfunction "S_1") (pintype "passive"))
      (node (ref "V1") (pin "16") (pinfunction "+UB_16") (pintype "power_in"))
      (node (ref "V2") (pin "16") (pinfunction "+UB_16") (pintype "power_in"))
      (node (ref "V3") (pin "16") (pinfunction "+UB_16") (pintype "power_in"))
    )
    (net (code "57") (name "XTAL1") (class "Default")
      (node (ref "C2") (pin "1") (pinfunction "1_1") (pintype "passive"))
      (node (ref "C3") (pin "1") (pinfunction "1_1") (pintype "passive"))
      (node (ref "IC1") (pin "7") (pinfunction "PB6(XTAL1/TOSC1/PCINT6)_7") (pintype "bidirectional"))
      (node (ref "Q1") (pin "2") (pinfunction "2_2") (pintype "passive"))
    )
    (net (code "58") (name "XTAL2") (class "Default")
      (node (ref "C2") (pin "2") (pinfunction "2_2") (pintype "passive"))
      (node (ref "C3") (pin "2") (pinfunction "2_2") (pintype "passive"))
      (node (ref "IC1") (pin "8") (pinfunction "PB7(XTAL2/TOSC2/PCINT7)_8") (pintype "bidirectional"))
      (node (ref "Q1") (pin "1") (pinfunction "1_1") (pintype "passive"))
    )
    (net (code "59") (name "unconnected-(ADD-P1-Pad4)") (class "Default")
      (node (ref "ADD") (pin "4") (pinfunction "P1_4") (pintype "passive"))
    )
    (net (code "60") (name "unconnected-(ADD-S1-Pad2)") (class "Default")
      (node (ref "ADD") (pin "2") (pinfunction "S1_2") (pintype "passive"))
    )
    (net (code "61") (name "unconnected-(IC1A-(PCINT0{slash}CLKO{slash}ICP1)PB0-Pad12)") (class "Default")
      (node (ref "IC1") (pin "12") (pinfunction "(PCINT0/CLKO/ICP1)PB0_12") (pintype "bidirectional"))
    )
    (net (code "62") (name "unconnected-(IC1A-(PCINT1{slash}OC1A)PB1-Pad13)") (class "Default")
      (node (ref "IC1") (pin "13") (pinfunction "(PCINT1/OC1A)PB1_13") (pintype "bidirectional"))
    )
    (net (code "63") (name "unconnected-(IC1A-ADC6-Pad19)") (class "Default")
      (node (ref "IC1") (pin "19") (pinfunction "ADC6_19") (pintype "bidirectional"))
    )
    (net (code "64") (name "unconnected-(IC1A-ADC7-Pad22)") (class "Default")
      (node (ref "IC1") (pin "22") (pinfunction "ADC7_22") (pintype "bidirectional"))
    )
    (net (code "65") (name "unconnected-(IC1A-PD6(AIN0{slash}OC0A{slash}PCINT22)-Pad10)") (class "Default")
      (node (ref "IC1") (pin "10") (pinfunction "PD6(AIN0/OC0A/PCINT22)_10") (pintype "bidirectional"))
    )
    (net (code "66") (name "unconnected-(IC1A-PD7(AIN1{slash}PCINT23)-Pad11)") (class "Default")
      (node (ref "IC1") (pin "11") (pinfunction "PD7(AIN1/PCINT23)_11") (pintype "bidirectional"))
    )
    (net (code "67") (name "unconnected-(IC2-SQW{slash}OUT-Pad7)") (class "Default")
      (node (ref "IC2") (pin "7") (pinfunction "SQW/OUT_7") (pintype "bidirectional"))
    )
    (net (code "68") (name "unconnected-(RESET-P1-Pad4)") (class "Default")
      (node (ref "RESET") (pin "4") (pinfunction "P1_4") (pintype "passive"))
    )
    (net (code "69") (name "unconnected-(RESET-S1-Pad2)") (class "Default")
      (node (ref "RESET") (pin "2") (pinfunction "S1_2") (pintype "passive"))
    )
    (net (code "70") (name "unconnected-(SET-P1-Pad4)") (class "Default")
      (node (ref "SET") (pin "4") (pinfunction "P1_4") (pintype "passive"))
    )
    (net (code "71") (name "unconnected-(SET-S1-Pad2)") (class "Default")
      (node (ref "SET") (pin "2") (pinfunction "S1_2") (pintype "passive"))
    )
    (net (code "72") (name "unconnected-(V1C-QH*-Pad9)") (class "Default")
      (node (ref "V1") (pin "9") (pinfunction "QH*_9") (pintype "output"))
    )
    (net (code "73") (name "unconnected-(V1C-QH-Pad7)") (class "Default")
      (node (ref "V1") (pin "7") (pinfunction "QH_7") (pintype "tri_state"))
    )
    (net (code "74") (name "unconnected-(V3C-QH*-Pad9)") (class "Default")
      (node (ref "V3") (pin "9") (pinfunction "QH*_9") (pintype "output"))
    )
    (net (code "75") (name "{slash}H_RST") (class "Default")
      (node (ref "R18") (pin "1") (pinfunction "1_1") (pintype "passive"))
      (node (ref "V1") (pin "10") (pinfunction "~{SRCLR}_10") (pintype "input"))
    )
    (net (code "76") (name "{slash}M_RST") (class "Default")
      (node (ref "R19") (pin "1") (pinfunction "1_1") (pintype "passive"))
      (node (ref "R20") (pin "1") (pinfunction "1_1") (pintype "passive"))
      (node (ref "V2") (pin "10") (pinfunction "~{SRCLR}_10") (pintype "input"))
      (node (ref "V3") (pin "10") (pinfunction "~{SRCLR}_10") (pintype "input"))
    )
    (net (code "77") (name "{slash}RST") (class "Default")
      (node (ref "IC1") (pin "29") (pinfunction "PC6(~{RESET}/PCINT14)_29") (pintype "bidirectional"))
      (node (ref "JP1") (pin "8") (pinfunction "8_8") (pintype "passive"))
      (node (ref "R13") (pin "1") (pinfunction "1_1") (pintype "passive"))
      (node (ref "RESET") (pin "3") (pinfunction "P_3") (pintype "passive"))
    )
    (net (code "78") (name "{slash}SPI_SS") (class "Default")
      (node (ref "IC1") (pin "14") (pinfunction "(PCINT2/OC1B/~{SS})PB2_14") (pintype "bidirectional"))
    )
  )
)
